# GamePad.net
KiCad netlist of a schematic drawn in EAGLE
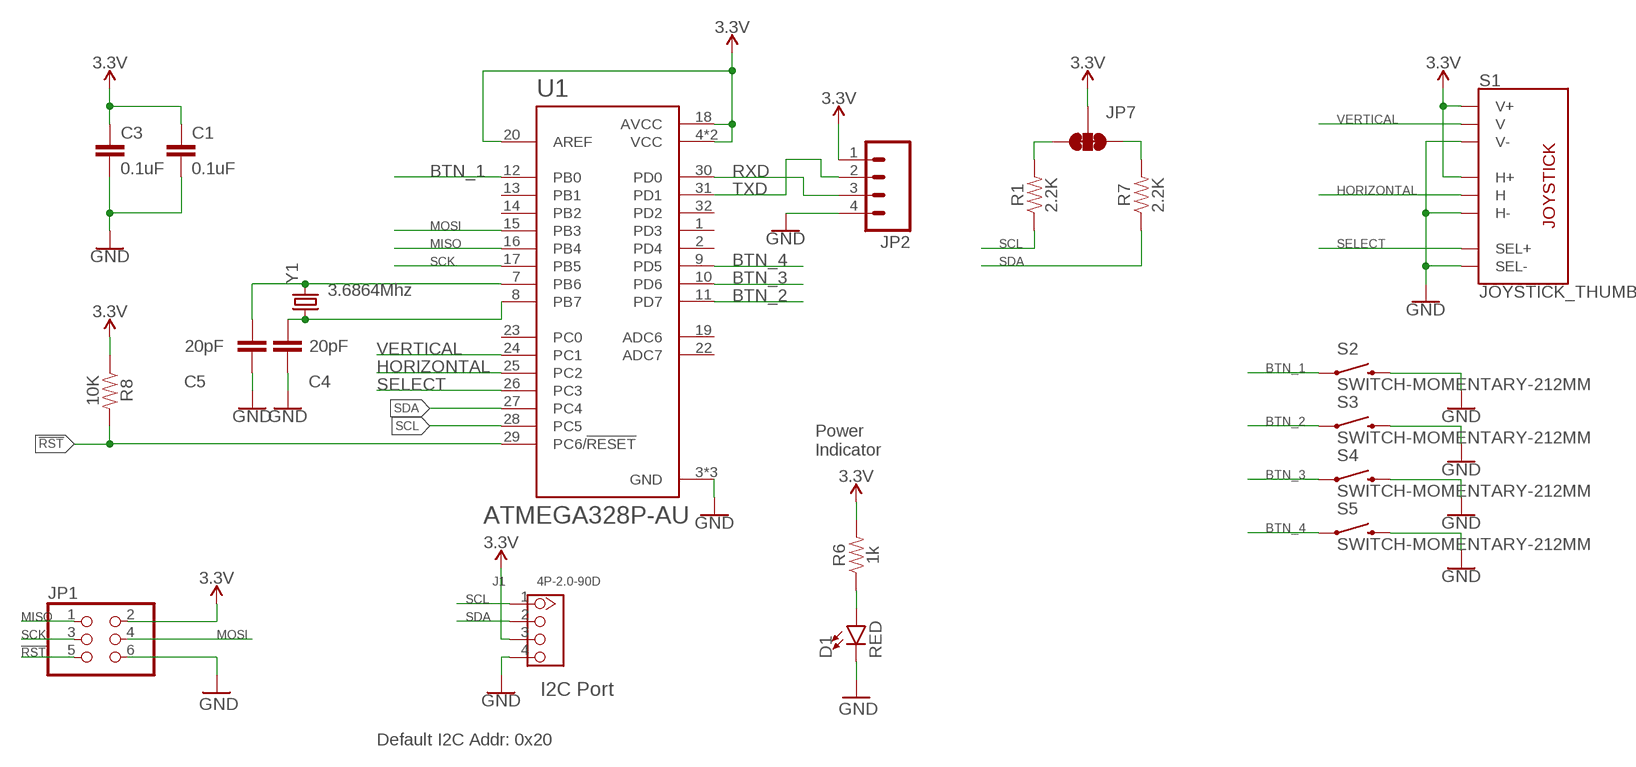
[diagram p0: schematic, sheet 1]

(export (version "E")
  (design (tool "Eeschema 10.0.6"))
  (components
    (comp (ref "C1")
      (value "0.1uF")
      (footprint "eagle-import:0603-CAP")
      (libsource (lib "eagle-import") (part "CAP0603-CAP"))
    )
    (comp (ref "C3")
      (value "0.1uF")
      (footprint "eagle-import:0603-CAP")
      (libsource (lib "eagle-import") (part "CAP0603-CAP"))
    )
    (comp (ref "C4")
      (value "20pF")
      (footprint "eagle-import:0603-CAP")
      (libsource (lib "eagle-import") (part "CAP0603-CAP"))
    )
    (comp (ref "C5")
      (value "20pF")
      (footprint "eagle-import:0603-CAP")
      (libsource (lib "eagle-import") (part "CAP0603-CAP"))
    )
    (comp (ref "D1")
      (value "RED")
      (footprint "eagle-import:LED-0603")
      (libsource (lib "eagle-import") (part "LED-RED0603"))
    )
    (comp (ref "J1")
      (value "4P-2.0-90D")
      (footprint "eagle-import:HW4-2.0-90D")
      (libsource (lib "eagle-import") (part "GROVE-CONNECTOR-DIP-90D(4P-2.0)"))
    )
    (comp (ref "JP1")
      (value "PINHD-2X3")
      (footprint "eagle-import:2X03")
      (libsource (lib "eagle-import") (part "PINHD-2X3"))
    )
    (comp (ref "JP2")
      (value "M04LOCK")
      (footprint "eagle-import:1X04_LOCK")
      (libsource (lib "eagle-import") (part "M04LOCK"))
    )
    (comp (ref "JP7")
      (value "JUMPER-SMT_3_2-NC_TRACE_NO-SILK")
      (footprint "eagle-import:SMT-JUMPER_3_2-NC_TRACE_NO-SILK")
      (libsource (lib "eagle-import") (part "JUMPER-SMT_3_2-NC_TRACE_NO-SILK"))
    )
    (comp (ref "R1")
      (value "2.2K")
      (footprint "eagle-import:0603")
      (libsource (lib "eagle-import") (part "4.7KOHM-0603-1/10W-1%"))
    )
    (comp (ref "R6")
      (value "1k")
      (footprint "eagle-import:0603")
      (libsource (lib "eagle-import") (part "1KOHM-0603-1/10W-1%"))
    )
    (comp (ref "R7")
      (value "2.2K")
      (footprint "eagle-import:0603")
      (libsource (lib "eagle-import") (part "4.7KOHM-0603-1/10W-1%"))
    )
    (comp (ref "R8")
      (value "10K")
      (footprint "eagle-import:0603")
      (libsource (lib "eagle-import") (part "330OHM-0603-1/10W-1%"))
    )
    (comp (ref "S1")
      (value "JOYSTICK_THUMB")
      (footprint "eagle-import:JOYSTICK")
      (libsource (lib "eagle-import") (part "JOYSTICK_THUMB"))
    )
    (comp (ref "S2")
      (value "SWITCH-MOMENTARY-212MM")
      (footprint "eagle-import:TACTILE-PTH-12MM")
      (libsource (lib "eagle-import") (part "SWITCH-MOMENTARY-212MM"))
    )
    (comp (ref "S3")
      (value "SWITCH-MOMENTARY-212MM")
      (footprint "eagle-import:TACTILE-PTH-12MM")
      (libsource (lib "eagle-import") (part "SWITCH-MOMENTARY-212MM"))
    )
    (comp (ref "S4")
      (value "SWITCH-MOMENTARY-212MM")
      (footprint "eagle-import:TACTILE-PTH-12MM")
      (libsource (lib "eagle-import") (part "SWITCH-MOMENTARY-212MM"))
    )
    (comp (ref "S5")
      (value "SWITCH-MOMENTARY-212MM")
      (footprint "eagle-import:TACTILE-PTH-12MM")
      (libsource (lib "eagle-import") (part "SWITCH-MOMENTARY-212MM"))
    )
    (comp (ref "U1")
      (value "ATMEGA328P-AU")
      (footprint "eagle-import:QFP80P900X900X120-32N")
      (fields (field (name "MF") "Microchip"))
      (libsource (lib "eagle-import") (part "ATMEGA328P-AU"))
    )
    (comp (ref "Y1")
      (value "3.6864Mhz")
      (footprint "eagle-import:HC49UP")
      (libsource (lib "eagle-import") (part "CRYSTALSMD"))
    )
  )
  (nets
    (net (code "1") (name "/BTN_1") (class "Default")
      (node (ref "S2") (pin "1") (pinfunction "1_1") (pintype "passive"))
      (node (ref "U1") (pin "12") (pinfunction "PB0_12") (pintype "bidirectional"))
    )
    (net (code "2") (name "/BTN_2") (class "Default")
      (node (ref "S3") (pin "1") (pinfunction "1_1") (pintype "passive"))
      (node (ref "U1") (pin "11") (pinfunction "PD7_11") (pintype "bidirectional"))
    )
    (net (code "3") (name "/BTN_3") (class "Default")
      (node (ref "S4") (pin "1") (pinfunction "1_1") (pintype "passive"))
      (node (ref "U1") (pin "10") (pinfunction "PD6_10") (pintype "bidirectional"))
    )
    (net (code "4") (name "/BTN_4") (class "Default")
      (node (ref "S5") (pin "1") (pinfunction "1_1") (pintype "passive"))
      (node (ref "U1") (pin "9") (pinfunction "PD5_9") (pintype "bidirectional"))
    )
    (net (code "5") (name "/HORIZONTAL") (class "Default")
      (node (ref "S1") (pin "H2") (pinfunction "H_H2") (pintype "bidirectional"))
      (node (ref "U1") (pin "25") (pinfunction "PC2_25") (pintype "bidirectional"))
    )
    (net (code "6") (name "/MISO") (class "Default")
      (node (ref "JP1") (pin "1") (pinfunction "1_1") (pintype "passive"))
      (node (ref "U1") (pin "16") (pinfunction "PB4_16") (pintype "bidirectional"))
    )
    (net (code "7") (name "/MOSI") (class "Default")
      (node (ref "JP1") (pin "4") (pinfunction "4_4") (pintype "passive"))
      (node (ref "U1") (pin "15") (pinfunction "PB3_15") (pintype "bidirectional"))
    )
    (net (code "8") (name "/RXD") (class "Default")
      (node (ref "JP2") (pin "3") (pinfunction "3_3") (pintype "passive"))
      (node (ref "U1") (pin "30") (pinfunction "PD0_30") (pintype "bidirectional"))
    )
    (net (code "9") (name "/SCK") (class "Default")
      (node (ref "JP1") (pin "3") (pinfunction "3_3") (pintype "passive"))
      (node (ref "U1") (pin "17") (pinfunction "PB5_17") (pintype "bidirectional"))
    )
    (net (code "10") (name "/SELECT") (class "Default")
      (node (ref "S1") (pin "B1A") (pinfunction "SEL+_B1A") (pintype "bidirectional"))
      (node (ref "U1") (pin "26") (pinfunction "PC3_26") (pintype "bidirectional"))
    )
    (net (code "11") (name "/TXD") (class "Default")
      (node (ref "JP2") (pin "2") (pinfunction "2_2") (pintype "passive"))
      (node (ref "U1") (pin "31") (pinfunction "PD1_31") (pintype "bidirectional"))
    )
    (net (code "12") (name "/VERTICAL") (class "Default")
      (node (ref "S1") (pin "V2") (pinfunction "V_V2") (pintype "bidirectional"))
      (node (ref "U1") (pin "24") (pinfunction "PC1_24") (pintype "bidirectional"))
    )
    (net (code "13") (name "/~{RST}") (class "Default")
      (node (ref "JP1") (pin "5") (pinfunction "5_5") (pintype "passive"))
      (node (ref "R8") (pin "2") (pinfunction "2_2") (pintype "passive"))
      (node (ref "U1") (pin "29") (pinfunction "PC6/~{RESET}_29") (pintype "bidirectional"))
    )
    (net (code "14") (name "3.3V") (class "Default")
      (node (ref "C1") (pin "1") (pinfunction "1_1") (pintype "passive"))
      (node (ref "C3") (pin "1") (pinfunction "1_1") (pintype "passive"))
      (node (ref "J1") (pin "3") (pinfunction "3_3") (pintype "bidirectional"))
      (node (ref "JP1") (pin "2") (pinfunction "2_2") (pintype "passive"))
      (node (ref "JP2") (pin "1") (pinfunction "1_1") (pintype "passive"))
      (node (ref "JP7") (pin "2") (pinfunction "2_2") (pintype "passive"))
      (node (ref "R6") (pin "2") (pinfunction "2_2") (pintype "passive"))
      (node (ref "R8") (pin "1") (pinfunction "1_1") (pintype "passive"))
      (node (ref "S1") (pin "H1") (pinfunction "H+_H1") (pintype "bidirectional"))
      (node (ref "S1") (pin "V1") (pinfunction "V+_V1") (pintype "bidirectional"))
      (node (ref "U1") (pin "18") (pinfunction "AVCC_18") (pintype "power_in"))
      (node (ref "U1") (pin "20") (pinfunction "AREF_20") (pintype "input"))
      (node (ref "U1") (pin "4") (pinfunction "VCC_4") (pintype "power_in"))
      (node (ref "U1") (pin "6") (pinfunction "VCC_6") (pintype "power_in"))
    )
    (net (code "15") (name "GND") (class "Default")
      (node (ref "C1") (pin "2") (pinfunction "2_2") (pintype "passive"))
      (node (ref "C3") (pin "2") (pinfunction "2_2") (pintype "passive"))
      (node (ref "C4") (pin "1") (pinfunction "1_1") (pintype "passive"))
      (node (ref "C5") (pin "1") (pinfunction "1_1") (pintype "passive"))
      (node (ref "D1") (pin "C") (pinfunction "C_C") (pintype "passive"))
      (node (ref "J1") (pin "4") (pinfunction "4_4") (pintype "bidirectional"))
      (node (ref "JP1") (pin "6") (pinfunction "6_6") (pintype "passive"))
      (node (ref "JP2") (pin "4") (pinfunction "4_4") (pintype "passive"))
      (node (ref "S1") (pin "B2A") (pinfunction "SEL-_B2A") (pintype "bidirectional"))
      (node (ref "S1") (pin "H3") (pinfunction "H-_H3") (pintype "bidirectional"))
      (node (ref "S1") (pin "V3") (pinfunction "V-_V3") (pintype "bidirectional"))
      (node (ref "S2") (pin "3") (pinfunction "2_3") (pintype "passive"))
      (node (ref "S3") (pin "3") (pinfunction "2_3") (pintype "passive"))
      (node (ref "S4") (pin "3") (pinfunction "2_3") (pintype "passive"))
      (node (ref "S5") (pin "3") (pinfunction "2_3") (pintype "passive"))
      (node (ref "U1") (pin "21") (pinfunction "GND_21") (pintype "power_in"))
      (node (ref "U1") (pin "3") (pinfunction "GND_3") (pintype "power_in"))
      (node (ref "U1") (pin "5") (pinfunction "GND_5") (pintype "power_in"))
    )
    (net (code "16") (name "Net-(D1-PadA)") (class "Default")
      (node (ref "D1") (pin "A") (pinfunction "A_A") (pintype "passive"))
      (node (ref "R6") (pin "1") (pinfunction "1_1") (pintype "passive"))
    )
    (net (code "17") (name "Net-(JP7-Pad1)") (class "Default")
      (node (ref "JP7") (pin "1") (pinfunction "1_1") (pintype "passive"))
      (node (ref "R7") (pin "2") (pinfunction "2_2") (pintype "passive"))
    )
    (net (code "18") (name "Net-(JP7-Pad3)") (class "Default")
      (node (ref "JP7") (pin "3") (pinfunction "3_3") (pintype "passive"))
      (node (ref "R1") (pin "2") (pinfunction "2_2") (pintype "passive"))
    )
    (net (code "19") (name "Net-(U1-PB6)") (class "Default")
      (node (ref "C5") (pin "2") (pinfunction "2_2") (pintype "passive"))
      (node (ref "U1") (pin "7") (pinfunction "PB6_7") (pintype "bidirectional"))
      (node (ref "Y1") (pin "2") (pinfunction "2_2") (pintype "passive"))
    )
    (net (code "20") (name "Net-(U1-PB7)") (class "Default")
      (node (ref "C4") (pin "2") (pinfunction "2_2") (pintype "passive"))
      (node (ref "U1") (pin "8") (pinfunction "PB7_8") (pintype "bidirectional"))
      (node (ref "Y1") (pin "1") (pinfunction "1_1") (pintype "passive"))
    )
    (net (code "21") (name "SCL") (class "Default")
      (node (ref "J1") (pin "1") (pinfunction "1_1") (pintype "bidirectional"))
      (node (ref "R1") (pin "1") (pinfunction "1_1") (pintype "passive"))
      (node (ref "U1") (pin "28") (pinfunction "PC5_28") (pintype "bidirectional"))
    )
    (net (code "22") (name "SDA") (class "Default")
      (node (ref "J1") (pin "2") (pinfunction "2_2") (pintype "bidirectional"))
      (node (ref "R7") (pin "1") (pinfunction "1_1") (pintype "passive"))
      (node (ref "U1") (pin "27") (pinfunction "PC4_27") (pintype "bidirectional"))
    )
    (net (code "23") (name "unconnected-(U1-ADC6-Pad19)") (class "Default")
      (node (ref "U1") (pin "19") (pinfunction "ADC6_19") (pintype "bidirectional"))
    )
    (net (code "24") (name "unconnected-(U1-ADC7-Pad22)") (class "Default")
      (node (ref "U1") (pin "22") (pinfunction "ADC7_22") (pintype "bidirectional"))
    )
    (net (code "25") (name "unconnected-(U1-PB1-Pad13)") (class "Default")
      (node (ref "U1") (pin "13") (pinfunction "PB1_13") (pintype "bidirectional"))
    )
    (net (code "26") (name "unconnected-(U1-PB2-Pad14)") (class "Default")
      (node (ref "U1") (pin "14") (pinfunction "PB2_14") (pintype "bidirectional"))
    )
    (net (code "27") (name "unconnected-(U1-PC0-Pad23)") (class "Default")
      (node (ref "U1") (pin "23") (pinfunction "PC0_23") (pintype "bidirectional"))
    )
    (net (code "28") (name "unconnected-(U1-PD2-Pad32)") (class "Default")
      (node (ref "U1") (pin "32") (pinfunction "PD2_32") (pintype "bidirectional"))
    )
    (net (code "29") (name "unconnected-(U1-PD3-Pad1)") (class "Default")
      (node (ref "U1") (pin "1") (pinfunction "PD3_1") (pintype "bidirectional"))
    )
    (net (code "30") (name "unconnected-(U1-PD4-Pad2)") (class "Default")
      (node (ref "U1") (pin "2") (pinfunction "PD4_2") (pintype "bidirectional"))
    )
  )
)
